# 7seg.net
KiCad netlist of a schematic drawn in EAGLE
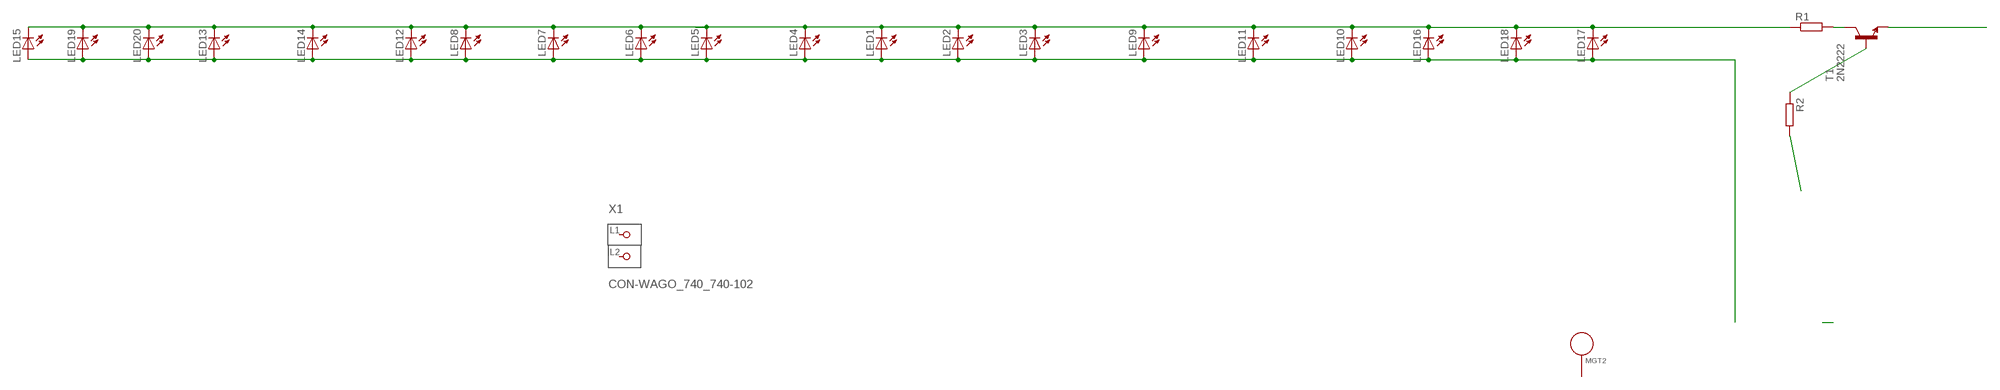
[diagram p0: schematic, sheet 1]
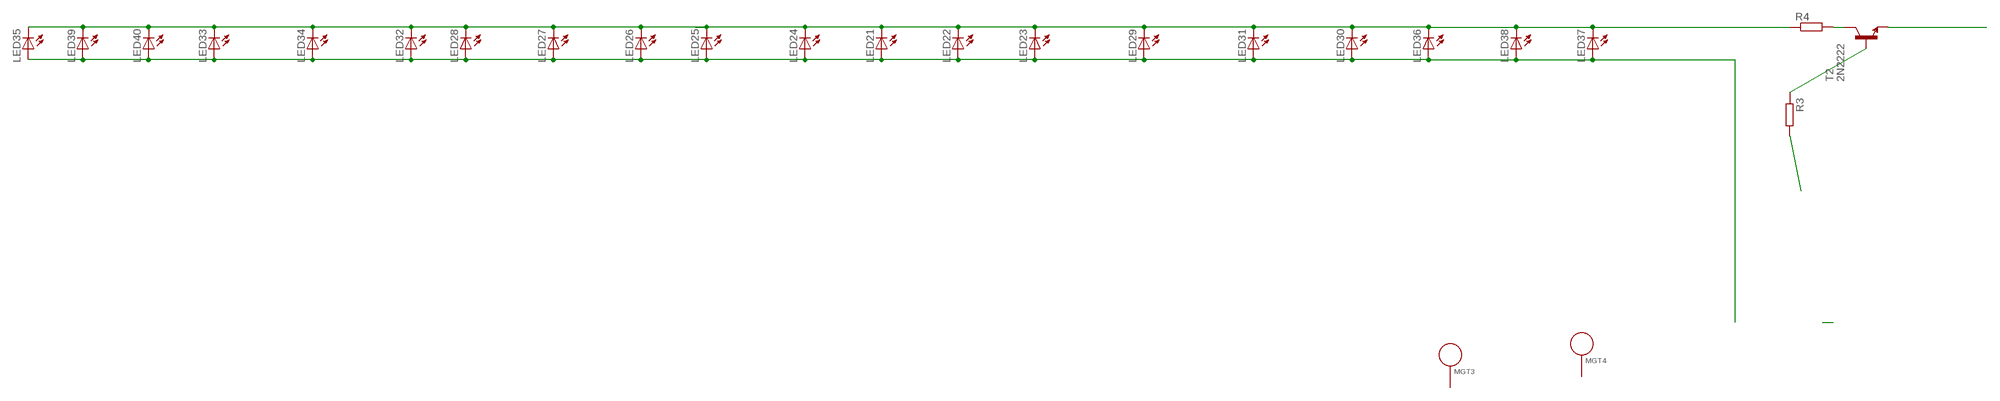
[diagram p1: schematic, sheet 2]
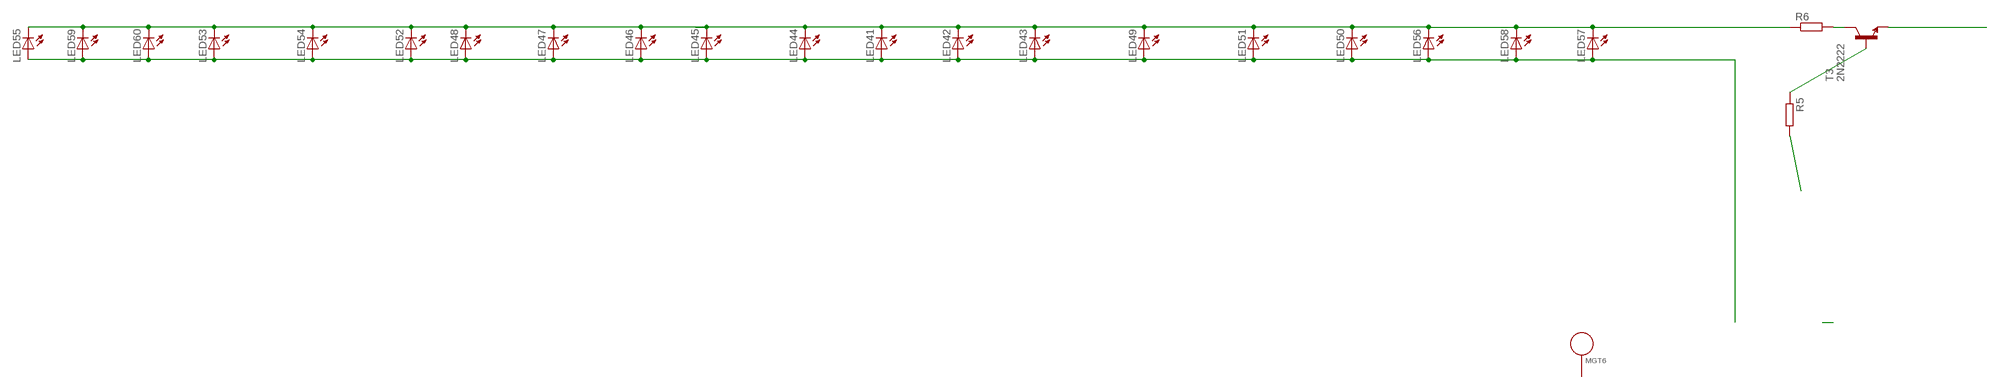
[diagram p2: schematic, sheet 3]
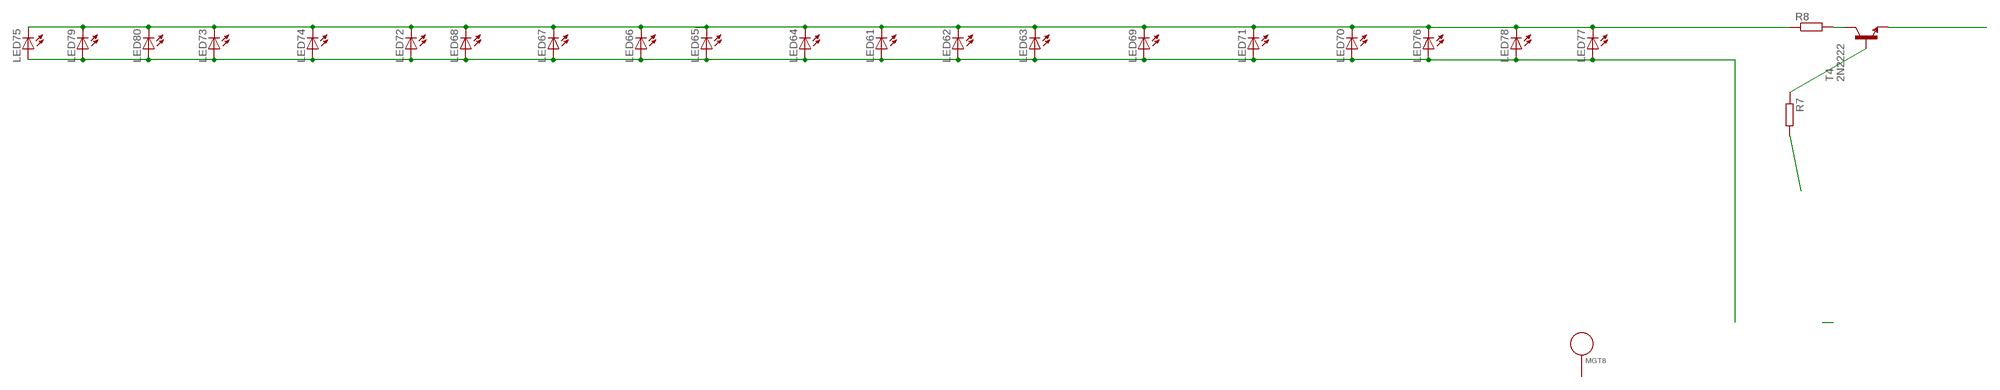
[diagram p3: schematic, sheet 4]
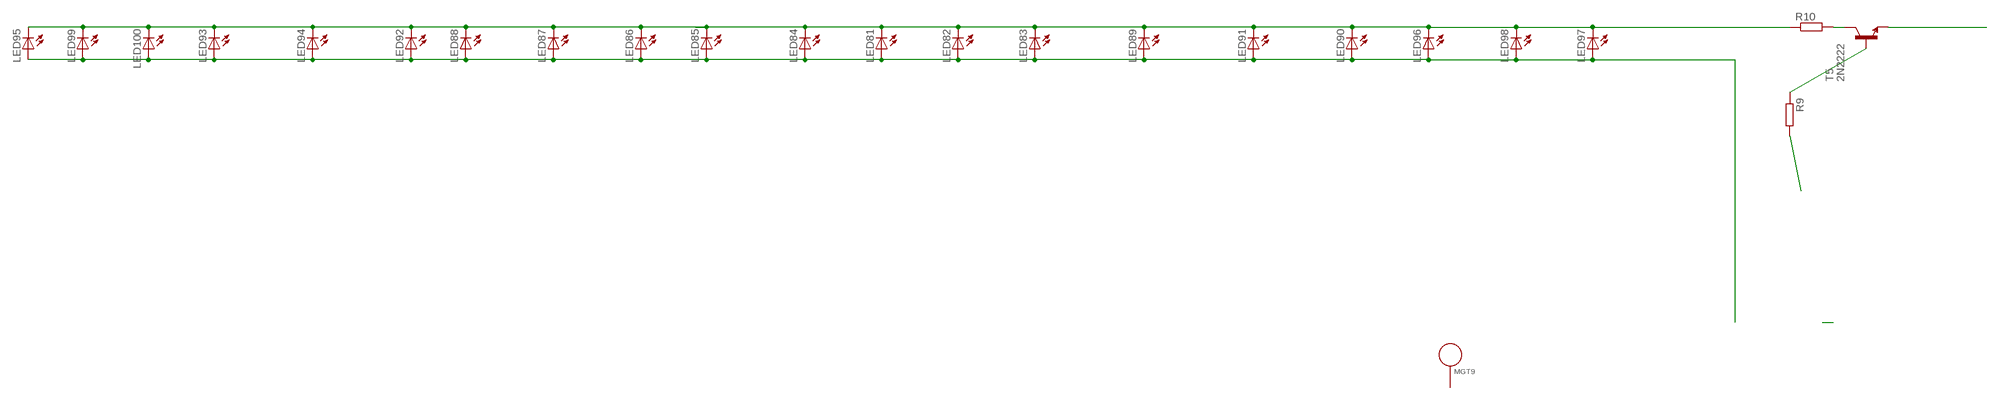
[diagram p4: schematic, sheet 5]
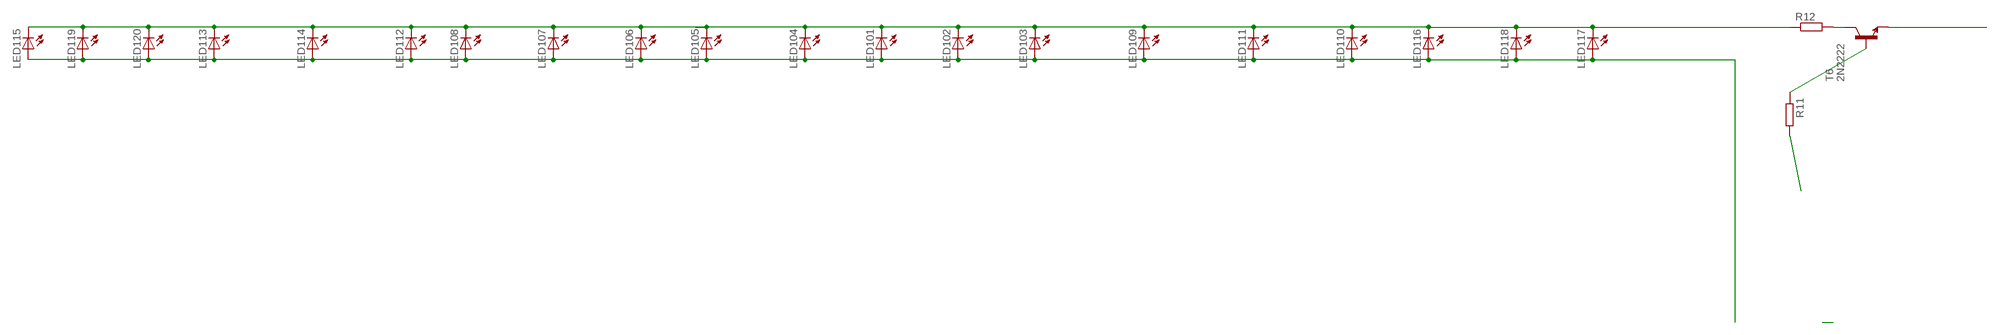
[diagram p5: schematic, sheet 6]
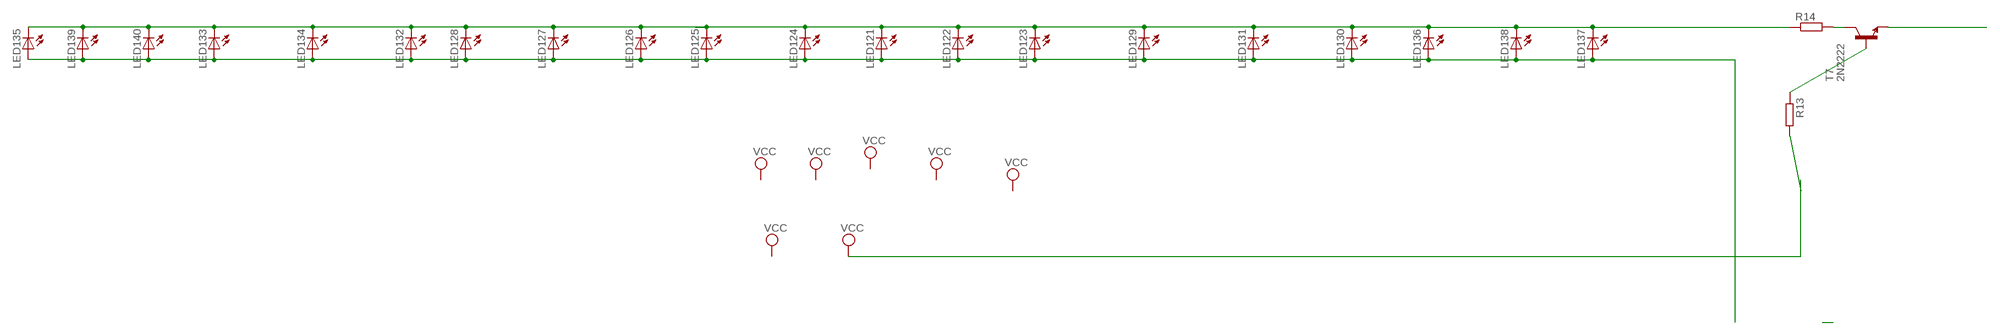
[diagram p6: schematic, sheet 7]

(export (version "E")
  (design (tool "Eeschema 10.0.6"))
  (components
    (comp (ref "LED21")
      (value "LED5MM")
      (footprint "eagle-import:LED5MM")
      (libsource (lib "eagle-import") (part "LED5MM"))
    )
    (comp (ref "LED22")
      (value "LED5MM")
      (footprint "eagle-import:LED5MM")
      (libsource (lib "eagle-import") (part "LED5MM"))
    )
    (comp (ref "LED23")
      (value "LED5MM")
      (footprint "eagle-import:LED5MM")
      (libsource (lib "eagle-import") (part "LED5MM"))
    )
    (comp (ref "LED24")
      (value "LED5MM")
      (footprint "eagle-import:LED5MM")
      (libsource (lib "eagle-import") (part "LED5MM"))
    )
    (comp (ref "LED25")
      (value "LED5MM")
      (footprint "eagle-import:LED5MM")
      (libsource (lib "eagle-import") (part "LED5MM"))
    )
    (comp (ref "LED26")
      (value "LED5MM")
      (footprint "eagle-import:LED5MM")
      (libsource (lib "eagle-import") (part "LED5MM"))
    )
    (comp (ref "LED27")
      (value "LED5MM")
      (footprint "eagle-import:LED5MM")
      (libsource (lib "eagle-import") (part "LED5MM"))
    )
    (comp (ref "LED28")
      (value "LED5MM")
      (footprint "eagle-import:LED5MM")
      (libsource (lib "eagle-import") (part "LED5MM"))
    )
    (comp (ref "LED29")
      (value "LED5MM")
      (footprint "eagle-import:LED5MM")
      (libsource (lib "eagle-import") (part "LED5MM"))
    )
    (comp (ref "LED30")
      (value "LED5MM")
      (footprint "eagle-import:LED5MM")
      (libsource (lib "eagle-import") (part "LED5MM"))
    )
    (comp (ref "LED31")
      (value "LED5MM")
      (footprint "eagle-import:LED5MM")
      (libsource (lib "eagle-import") (part "LED5MM"))
    )
    (comp (ref "LED32")
      (value "LED5MM")
      (footprint "eagle-import:LED5MM")
      (libsource (lib "eagle-import") (part "LED5MM"))
    )
    (comp (ref "LED33")
      (value "LED5MM")
      (footprint "eagle-import:LED5MM")
      (libsource (lib "eagle-import") (part "LED5MM"))
    )
    (comp (ref "LED34")
      (value "LED5MM")
      (footprint "eagle-import:LED5MM")
      (libsource (lib "eagle-import") (part "LED5MM"))
    )
    (comp (ref "LED35")
      (value "LED5MM")
      (footprint "eagle-import:LED5MM")
      (libsource (lib "eagle-import") (part "LED5MM"))
    )
    (comp (ref "LED36")
      (value "LED5MM")
      (footprint "eagle-import:LED5MM")
      (libsource (lib "eagle-import") (part "LED5MM"))
    )
    (comp (ref "LED37")
      (value "LED5MM")
      (footprint "eagle-import:LED5MM")
      (libsource (lib "eagle-import") (part "LED5MM"))
    )
    (comp (ref "LED38")
      (value "LED5MM")
      (footprint "eagle-import:LED5MM")
      (libsource (lib "eagle-import") (part "LED5MM"))
    )
    (comp (ref "LED39")
      (value "LED5MM")
      (footprint "eagle-import:LED5MM")
      (libsource (lib "eagle-import") (part "LED5MM"))
    )
    (comp (ref "LED40")
      (value "LED5MM")
      (footprint "eagle-import:LED5MM")
      (libsource (lib "eagle-import") (part "LED5MM"))
    )
    (comp (ref "MGT3")
      (value "BEAGLEBONEBLACK_MOUNTING_HOLE")
      (footprint "eagle-import:BEAGLEBONEBLACK_MOUNTING_HOLE")
      (libsource (lib "eagle-import") (part "BEAGLEBONEBLACK_MOUNTING_HOLE"))
    )
    (comp (ref "MGT4")
      (value "BEAGLEBONEBLACK_MOUNTING_HOLE")
      (footprint "eagle-import:BEAGLEBONEBLACK_MOUNTING_HOLE")
      (libsource (lib "eagle-import") (part "BEAGLEBONEBLACK_MOUNTING_HOLE"))
    )
    (comp (ref "R3")
      (value "R-EU_0207/10")
      (footprint "eagle-import:0207_10")
      (libsource (lib "eagle-import") (part "R-EU_0207/10"))
    )
    (comp (ref "R4")
      (value "R-EU_0207/10")
      (footprint "eagle-import:0207_10")
      (libsource (lib "eagle-import") (part "R-EU_0207/10"))
    )
    (comp (ref "T2")
      (value "2N2222")
      (footprint "eagle-import:TO92-EBC-OVAL")
      (libsource (lib "eagle-import") (part "2N2222"))
    )
    (comp (ref "LED41")
      (value "LED5MM")
      (footprint "eagle-import:LED5MM")
      (libsource (lib "eagle-import") (part "LED5MM"))
    )
    (comp (ref "LED42")
      (value "LED5MM")
      (footprint "eagle-import:LED5MM")
      (libsource (lib "eagle-import") (part "LED5MM"))
    )
    (comp (ref "LED43")
      (value "LED5MM")
      (footprint "eagle-import:LED5MM")
      (libsource (lib "eagle-import") (part "LED5MM"))
    )
    (comp (ref "LED44")
      (value "LED5MM")
      (footprint "eagle-import:LED5MM")
      (libsource (lib "eagle-import") (part "LED5MM"))
    )
    (comp (ref "LED45")
      (value "LED5MM")
      (footprint "eagle-import:LED5MM")
      (libsource (lib "eagle-import") (part "LED5MM"))
    )
    (comp (ref "LED46")
      (value "LED5MM")
      (footprint "eagle-import:LED5MM")
      (libsource (lib "eagle-import") (part "LED5MM"))
    )
    (comp (ref "LED47")
      (value "LED5MM")
      (footprint "eagle-import:LED5MM")
      (libsource (lib "eagle-import") (part "LED5MM"))
    )
    (comp (ref "LED48")
      (value "LED5MM")
      (footprint "eagle-import:LED5MM")
      (libsource (lib "eagle-import") (part "LED5MM"))
    )
    (comp (ref "LED49")
      (value "LED5MM")
      (footprint "eagle-import:LED5MM")
      (libsource (lib "eagle-import") (part "LED5MM"))
    )
    (comp (ref "LED50")
      (value "LED5MM")
      (footprint "eagle-import:LED5MM")
      (libsource (lib "eagle-import") (part "LED5MM"))
    )
    (comp (ref "LED51")
      (value "LED5MM")
      (footprint "eagle-import:LED5MM")
      (libsource (lib "eagle-import") (part "LED5MM"))
    )
    (comp (ref "LED52")
      (value "LED5MM")
      (footprint "eagle-import:LED5MM")
      (libsource (lib "eagle-import") (part "LED5MM"))
    )
    (comp (ref "LED53")
      (value "LED5MM")
      (footprint "eagle-import:LED5MM")
      (libsource (lib "eagle-import") (part "LED5MM"))
    )
    (comp (ref "LED54")
      (value "LED5MM")
      (footprint "eagle-import:LED5MM")
      (libsource (lib "eagle-import") (part "LED5MM"))
    )
    (comp (ref "LED55")
      (value "LED5MM")
      (footprint "eagle-import:LED5MM")
      (libsource (lib "eagle-import") (part "LED5MM"))
    )
    (comp (ref "LED56")
      (value "LED5MM")
      (footprint "eagle-import:LED5MM")
      (libsource (lib "eagle-import") (part "LED5MM"))
    )
    (comp (ref "LED57")
      (value "LED5MM")
      (footprint "eagle-import:LED5MM")
      (libsource (lib "eagle-import") (part "LED5MM"))
    )
    (comp (ref "LED58")
      (value "LED5MM")
      (footprint "eagle-import:LED5MM")
      (libsource (lib "eagle-import") (part "LED5MM"))
    )
    (comp (ref "LED59")
      (value "LED5MM")
      (footprint "eagle-import:LED5MM")
      (libsource (lib "eagle-import") (part "LED5MM"))
    )
    (comp (ref "LED60")
      (value "LED5MM")
      (footprint "eagle-import:LED5MM")
      (libsource (lib "eagle-import") (part "LED5MM"))
    )
    (comp (ref "MGT6")
      (value "BEAGLEBONEBLACK_MOUNTING_HOLE")
      (footprint "eagle-import:BEAGLEBONEBLACK_MOUNTING_HOLE")
      (libsource (lib "eagle-import") (part "BEAGLEBONEBLACK_MOUNTING_HOLE"))
    )
    (comp (ref "R5")
      (value "R-EU_0207/10")
      (footprint "eagle-import:0207_10")
      (libsource (lib "eagle-import") (part "R-EU_0207/10"))
    )
    (comp (ref "R6")
      (value "R-EU_0207/10")
      (footprint "eagle-import:0207_10")
      (libsource (lib "eagle-import") (part "R-EU_0207/10"))
    )
    (comp (ref "T3")
      (value "2N2222")
      (footprint "eagle-import:TO92-EBC-OVAL")
      (libsource (lib "eagle-import") (part "2N2222"))
    )
    (comp (ref "LED61")
      (value "LED5MM")
      (footprint "eagle-import:LED5MM")
      (libsource (lib "eagle-import") (part "LED5MM"))
    )
    (comp (ref "LED62")
      (value "LED5MM")
      (footprint "eagle-import:LED5MM")
      (libsource (lib "eagle-import") (part "LED5MM"))
    )
    (comp (ref "LED63")
      (value "LED5MM")
      (footprint "eagle-import:LED5MM")
      (libsource (lib "eagle-import") (part "LED5MM"))
    )
    (comp (ref "LED64")
      (value "LED5MM")
      (footprint "eagle-import:LED5MM")
      (libsource (lib "eagle-import") (part "LED5MM"))
    )
    (comp (ref "LED65")
      (value "LED5MM")
      (footprint "eagle-import:LED5MM")
      (libsource (lib "eagle-import") (part "LED5MM"))
    )
    (comp (ref "LED66")
      (value "LED5MM")
      (footprint "eagle-import:LED5MM")
      (libsource (lib "eagle-import") (part "LED5MM"))
    )
    (comp (ref "LED67")
      (value "LED5MM")
      (footprint "eagle-import:LED5MM")
      (libsource (lib "eagle-import") (part "LED5MM"))
    )
    (comp (ref "LED68")
      (value "LED5MM")
      (footprint "eagle-import:LED5MM")
      (libsource (lib "eagle-import") (part "LED5MM"))
    )
    (comp (ref "LED69")
      (value "LED5MM")
      (footprint "eagle-import:LED5MM")
      (libsource (lib "eagle-import") (part "LED5MM"))
    )
    (comp (ref "LED70")
      (value "LED5MM")
      (footprint "eagle-import:LED5MM")
      (libsource (lib "eagle-import") (part "LED5MM"))
    )
    (comp (ref "LED71")
      (value "LED5MM")
      (footprint "eagle-import:LED5MM")
      (libsource (lib "eagle-import") (part "LED5MM"))
    )
    (comp (ref "LED72")
      (value "LED5MM")
      (footprint "eagle-import:LED5MM")
      (libsource (lib "eagle-import") (part "LED5MM"))
    )
    (comp (ref "LED73")
      (value "LED5MM")
      (footprint "eagle-import:LED5MM")
      (libsource (lib "eagle-import") (part "LED5MM"))
    )
    (comp (ref "LED74")
      (value "LED5MM")
      (footprint "eagle-import:LED5MM")
      (libsource (lib "eagle-import") (part "LED5MM"))
    )
    (comp (ref "LED75")
      (value "LED5MM")
      (footprint "eagle-import:LED5MM")
      (libsource (lib "eagle-import") (part "LED5MM"))
    )
    (comp (ref "LED76")
      (value "LED5MM")
      (footprint "eagle-import:LED5MM")
      (libsource (lib "eagle-import") (part "LED5MM"))
    )
    (comp (ref "LED77")
      (value "LED5MM")
      (footprint "eagle-import:LED5MM")
      (libsource (lib "eagle-import") (part "LED5MM"))
    )
    (comp (ref "LED78")
      (value "LED5MM")
      (footprint "eagle-import:LED5MM")
      (libsource (lib "eagle-import") (part "LED5MM"))
    )
    (comp (ref "LED79")
      (value "LED5MM")
      (footprint "eagle-import:LED5MM")
      (libsource (lib "eagle-import") (part "LED5MM"))
    )
    (comp (ref "LED80")
      (value "LED5MM")
      (footprint "eagle-import:LED5MM")
      (libsource (lib "eagle-import") (part "LED5MM"))
    )
    (comp (ref "MGT8")
      (value "BEAGLEBONEBLACK_MOUNTING_HOLE")
      (footprint "eagle-import:BEAGLEBONEBLACK_MOUNTING_HOLE")
      (libsource (lib "eagle-import") (part "BEAGLEBONEBLACK_MOUNTING_HOLE"))
    )
    (comp (ref "R7")
      (value "R-EU_0207/10")
      (footprint "eagle-import:0207_10")
      (libsource (lib "eagle-import") (part "R-EU_0207/10"))
    )
    (comp (ref "R8")
      (value "R-EU_0207/10")
      (footprint "eagle-import:0207_10")
      (libsource (lib "eagle-import") (part "R-EU_0207/10"))
    )
    (comp (ref "T4")
      (value "2N2222")
      (footprint "eagle-import:TO92-EBC-OVAL")
      (libsource (lib "eagle-import") (part "2N2222"))
    )
    (comp (ref "LED101")
      (value "LED5MM")
      (footprint "eagle-import:LED5MM")
      (libsource (lib "eagle-import") (part "LED5MM"))
    )
    (comp (ref "LED102")
      (value "LED5MM")
      (footprint "eagle-import:LED5MM")
      (libsource (lib "eagle-import") (part "LED5MM"))
    )
    (comp (ref "LED103")
      (value "LED5MM")
      (footprint "eagle-import:LED5MM")
      (libsource (lib "eagle-import") (part "LED5MM"))
    )
    (comp (ref "LED104")
      (value "LED5MM")
      (footprint "eagle-import:LED5MM")
      (libsource (lib "eagle-import") (part "LED5MM"))
    )
    (comp (ref "LED105")
      (value "LED5MM")
      (footprint "eagle-import:LED5MM")
      (libsource (lib "eagle-import") (part "LED5MM"))
    )
    (comp (ref "LED106")
      (value "LED5MM")
      (footprint "eagle-import:LED5MM")
      (libsource (lib "eagle-import") (part "LED5MM"))
    )
    (comp (ref "LED107")
      (value "LED5MM")
      (footprint "eagle-import:LED5MM")
      (libsource (lib "eagle-import") (part "LED5MM"))
    )
    (comp (ref "LED108")
      (value "LED5MM")
      (footprint "eagle-import:LED5MM")
      (libsource (lib "eagle-import") (part "LED5MM"))
    )
    (comp (ref "LED109")
      (value "LED5MM")
      (footprint "eagle-import:LED5MM")
      (libsource (lib "eagle-import") (part "LED5MM"))
    )
    (comp (ref "LED110")
      (value "LED5MM")
      (footprint "eagle-import:LED5MM")
      (libsource (lib "eagle-import") (part "LED5MM"))
    )
    (comp (ref "LED111")
      (value "LED5MM")
      (footprint "eagle-import:LED5MM")
      (libsource (lib "eagle-import") (part "LED5MM"))
    )
    (comp (ref "LED112")
      (value "LED5MM")
      (footprint "eagle-import:LED5MM")
      (libsource (lib "eagle-import") (part "LED5MM"))
    )
    (comp (ref "LED113")
      (value "LED5MM")
      (footprint "eagle-import:LED5MM")
      (libsource (lib "eagle-import") (part "LED5MM"))
    )
    (comp (ref "LED114")
      (value "LED5MM")
      (footprint "eagle-import:LED5MM")
      (libsource (lib "eagle-import") (part "LED5MM"))
    )
    (comp (ref "LED115")
      (value "LED5MM")
      (footprint "eagle-import:LED5MM")
      (libsource (lib "eagle-import") (part "LED5MM"))
    )
    (comp (ref "LED116")
      (value "LED5MM")
      (footprint "eagle-import:LED5MM")
      (libsource (lib "eagle-import") (part "LED5MM"))
    )
    (comp (ref "LED117")
      (value "LED5MM")
      (footprint "eagle-import:LED5MM")
      (libsource (lib "eagle-import") (part "LED5MM"))
    )
    (comp (ref "LED118")
      (value "LED5MM")
      (footprint "eagle-import:LED5MM")
      (libsource (lib "eagle-import") (part "LED5MM"))
    )
    (comp (ref "LED119")
      (value "LED5MM")
      (footprint "eagle-import:LED5MM")
      (libsource (lib "eagle-import") (part "LED5MM"))
    )
    (comp (ref "LED120")
      (value "LED5MM")
      (footprint "eagle-import:LED5MM")
      (libsource (lib "eagle-import") (part "LED5MM"))
    )
    (comp (ref "R11")
      (value "R-EU_0207/10")
      (footprint "eagle-import:0207_10")
      (libsource (lib "eagle-import") (part "R-EU_0207/10"))
    )
    (comp (ref "R12")
      (value "R-EU_0207/10")
      (footprint "eagle-import:0207_10")
      (libsource (lib "eagle-import") (part "R-EU_0207/10"))
    )
    (comp (ref "T6")
      (value "2N2222")
      (footprint "eagle-import:TO92-EBC-OVAL")
      (libsource (lib "eagle-import") (part "2N2222"))
    )
    (comp (ref "LED1")
      (value "LED5MM")
      (footprint "eagle-import:LED5MM")
      (libsource (lib "eagle-import") (part "LED5MM"))
    )
    (comp (ref "LED2")
      (value "LED5MM")
      (footprint "eagle-import:LED5MM")
      (libsource (lib "eagle-import") (part "LED5MM"))
    )
    (comp (ref "LED3")
      (value "LED5MM")
      (footprint "eagle-import:LED5MM")
      (libsource (lib "eagle-import") (part "LED5MM"))
    )
    (comp (ref "LED4")
      (value "LED5MM")
      (footprint "eagle-import:LED5MM")
      (libsource (lib "eagle-import") (part "LED5MM"))
    )
    (comp (ref "LED5")
      (value "LED5MM")
      (footprint "eagle-import:LED5MM")
      (libsource (lib "eagle-import") (part "LED5MM"))
    )
    (comp (ref "LED6")
      (value "LED5MM")
      (footprint "eagle-import:LED5MM")
      (libsource (lib "eagle-import") (part "LED5MM"))
    )
    (comp (ref "LED7")
      (value "LED5MM")
      (footprint "eagle-import:LED5MM")
      (libsource (lib "eagle-import") (part "LED5MM"))
    )
    (comp (ref "LED8")
      (value "LED5MM")
      (footprint "eagle-import:LED5MM")
      (libsource (lib "eagle-import") (part "LED5MM"))
    )
    (comp (ref "LED9")
      (value "LED5MM")
      (footprint "eagle-import:LED5MM")
      (libsource (lib "eagle-import") (part "LED5MM"))
    )
    (comp (ref "LED10")
      (value "LED5MM")
      (footprint "eagle-import:LED5MM")
      (libsource (lib "eagle-import") (part "LED5MM"))
    )
    (comp (ref "LED11")
      (value "LED5MM")
      (footprint "eagle-import:LED5MM")
      (libsource (lib "eagle-import") (part "LED5MM"))
    )
    (comp (ref "LED12")
      (value "LED5MM")
      (footprint "eagle-import:LED5MM")
      (libsource (lib "eagle-import") (part "LED5MM"))
    )
    (comp (ref "LED13")
      (value "LED5MM")
      (footprint "eagle-import:LED5MM")
      (libsource (lib "eagle-import") (part "LED5MM"))
    )
    (comp (ref "LED14")
      (value "LED5MM")
      (footprint "eagle-import:LED5MM")
      (libsource (lib "eagle-import") (part "LED5MM"))
    )
    (comp (ref "LED15")
      (value "LED5MM")
      (footprint "eagle-import:LED5MM")
      (libsource (lib "eagle-import") (part "LED5MM"))
    )
    (comp (ref "LED16")
      (value "LED5MM")
      (footprint "eagle-import:LED5MM")
      (libsource (lib "eagle-import") (part "LED5MM"))
    )
    (comp (ref "LED17")
      (value "LED5MM")
      (footprint "eagle-import:LED5MM")
      (libsource (lib "eagle-import") (part "LED5MM"))
    )
    (comp (ref "LED18")
      (value "LED5MM")
      (footprint "eagle-import:LED5MM")
      (libsource (lib "eagle-import") (part "LED5MM"))
    )
    (comp (ref "LED19")
      (value "LED5MM")
      (footprint "eagle-import:LED5MM")
      (libsource (lib "eagle-import") (part "LED5MM"))
    )
    (comp (ref "LED20")
      (value "LED5MM")
      (footprint "eagle-import:LED5MM")
      (libsource (lib "eagle-import") (part "LED5MM"))
    )
    (comp (ref "MGT2")
      (value "BEAGLEBONEBLACK_MOUNTING_HOLE")
      (footprint "eagle-import:BEAGLEBONEBLACK_MOUNTING_HOLE")
      (libsource (lib "eagle-import") (part "BEAGLEBONEBLACK_MOUNTING_HOLE"))
    )
    (comp (ref "R1")
      (value "R-EU_0207/10")
      (footprint "eagle-import:0207_10")
      (libsource (lib "eagle-import") (part "R-EU_0207/10"))
    )
    (comp (ref "R2")
      (value "R-EU_0207/10")
      (footprint "eagle-import:0207_10")
      (libsource (lib "eagle-import") (part "R-EU_0207/10"))
    )
    (comp (ref "T1")
      (value "2N2222")
      (footprint "eagle-import:TO92-EBC-OVAL")
      (libsource (lib "eagle-import") (part "2N2222"))
    )
    (comp (ref "X1")
      (value "CON-WAGO_740_740-102")
      (footprint "eagle-import:CON-WAGO_740_P-740-102")
      (libsource (lib "eagle-import") (part "CON-WAGO_740_740-102"))
    )
    (comp (ref "LED121")
      (value "LED5MM")
      (footprint "eagle-import:LED5MM")
      (libsource (lib "eagle-import") (part "LED5MM"))
    )
    (comp (ref "LED122")
      (value "LED5MM")
      (footprint "eagle-import:LED5MM")
      (libsource (lib "eagle-import") (part "LED5MM"))
    )
    (comp (ref "LED123")
      (value "LED5MM")
      (footprint "eagle-import:LED5MM")
      (libsource (lib "eagle-import") (part "LED5MM"))
    )
    (comp (ref "LED124")
      (value "LED5MM")
      (footprint "eagle-import:LED5MM")
      (libsource (lib "eagle-import") (part "LED5MM"))
    )
    (comp (ref "LED125")
      (value "LED5MM")
      (footprint "eagle-import:LED5MM")
      (libsource (lib "eagle-import") (part "LED5MM"))
    )
    (comp (ref "LED126")
      (value "LED5MM")
      (footprint "eagle-import:LED5MM")
      (libsource (lib "eagle-import") (part "LED5MM"))
    )
    (comp (ref "LED127")
      (value "LED5MM")
      (footprint "eagle-import:LED5MM")
      (libsource (lib "eagle-import") (part "LED5MM"))
    )
    (comp (ref "LED128")
      (value "LED5MM")
      (footprint "eagle-import:LED5MM")
      (libsource (lib "eagle-import") (part "LED5MM"))
    )
    (comp (ref "LED129")
      (value "LED5MM")
      (footprint "eagle-import:LED5MM")
      (libsource (lib "eagle-import") (part "LED5MM"))
    )
    (comp (ref "LED130")
      (value "LED5MM")
      (footprint "eagle-import:LED5MM")
      (libsource (lib "eagle-import") (part "LED5MM"))
    )
    (comp (ref "LED131")
      (value "LED5MM")
      (footprint "eagle-import:LED5MM")
      (libsource (lib "eagle-import") (part "LED5MM"))
    )
    (comp (ref "LED132")
      (value "LED5MM")
      (footprint "eagle-import:LED5MM")
      (libsource (lib "eagle-import") (part "LED5MM"))
    )
    (comp (ref "LED133")
      (value "LED5MM")
      (footprint "eagle-import:LED5MM")
      (libsource (lib "eagle-import") (part "LED5MM"))
    )
    (comp (ref "LED134")
      (value "LED5MM")
      (footprint "eagle-import:LED5MM")
      (libsource (lib "eagle-import") (part "LED5MM"))
    )
    (comp (ref "LED135")
      (value "LED5MM")
      (footprint "eagle-import:LED5MM")
      (libsource (lib "eagle-import") (part "LED5MM"))
    )
    (comp (ref "LED136")
      (value "LED5MM")
      (footprint "eagle-import:LED5MM")
      (libsource (lib "eagle-import") (part "LED5MM"))
    )
    (comp (ref "LED137")
      (value "LED5MM")
      (footprint "eagle-import:LED5MM")
      (libsource (lib "eagle-import") (part "LED5MM"))
    )
    (comp (ref "LED138")
      (value "LED5MM")
      (footprint "eagle-import:LED5MM")
      (libsource (lib "eagle-import") (part "LED5MM"))
    )
    (comp (ref "LED139")
      (value "LED5MM")
      (footprint "eagle-import:LED5MM")
      (libsource (lib "eagle-import") (part "LED5MM"))
    )
    (comp (ref "LED140")
      (value "LED5MM")
      (footprint "eagle-import:LED5MM")
      (libsource (lib "eagle-import") (part "LED5MM"))
    )
    (comp (ref "R13")
      (value "R-EU_0207/10")
      (footprint "eagle-import:0207_10")
      (libsource (lib "eagle-import") (part "R-EU_0207/10"))
    )
    (comp (ref "R14")
      (value "R-EU_0207/10")
      (footprint "eagle-import:0207_10")
      (libsource (lib "eagle-import") (part "R-EU_0207/10"))
    )
    (comp (ref "T7")
      (value "2N2222")
      (footprint "eagle-import:TO92-EBC-OVAL")
      (libsource (lib "eagle-import") (part "2N2222"))
    )
    (comp (ref "LED81")
      (value "LED5MM")
      (footprint "eagle-import:LED5MM")
      (libsource (lib "eagle-import") (part "LED5MM"))
    )
    (comp (ref "LED82")
      (value "LED5MM")
      (footprint "eagle-import:LED5MM")
      (libsource (lib "eagle-import") (part "LED5MM"))
    )
    (comp (ref "LED83")
      (value "LED5MM")
      (footprint "eagle-import:LED5MM")
      (libsource (lib "eagle-import") (part "LED5MM"))
    )
    (comp (ref "LED84")
      (value "LED5MM")
      (footprint "eagle-import:LED5MM")
      (libsource (lib "eagle-import") (part "LED5MM"))
    )
    (comp (ref "LED85")
      (value "LED5MM")
      (footprint "eagle-import:LED5MM")
      (libsource (lib "eagle-import") (part "LED5MM"))
    )
    (comp (ref "LED86")
      (value "LED5MM")
      (footprint "eagle-import:LED5MM")
      (libsource (lib "eagle-import") (part "LED5MM"))
    )
    (comp (ref "LED87")
      (value "LED5MM")
      (footprint "eagle-import:LED5MM")
      (libsource (lib "eagle-import") (part "LED5MM"))
    )
    (comp (ref "LED88")
      (value "LED5MM")
      (footprint "eagle-import:LED5MM")
      (libsource (lib "eagle-import") (part "LED5MM"))
    )
    (comp (ref "LED89")
      (value "LED5MM")
      (footprint "eagle-import:LED5MM")
      (libsource (lib "eagle-import") (part "LED5MM"))
    )
    (comp (ref "LED90")
      (value "LED5MM")
      (footprint "eagle-import:LED5MM")
      (libsource (lib "eagle-import") (part "LED5MM"))
    )
    (comp (ref "LED91")
      (value "LED5MM")
      (footprint "eagle-import:LED5MM")
      (libsource (lib "eagle-import") (part "LED5MM"))
    )
    (comp (ref "LED92")
      (value "LED5MM")
      (footprint "eagle-import:LED5MM")
      (libsource (lib "eagle-import") (part "LED5MM"))
    )
    (comp (ref "LED93")
      (value "LED5MM")
      (footprint "eagle-import:LED5MM")
      (libsource (lib "eagle-import") (part "LED5MM"))
    )
    (comp (ref "LED94")
      (value "LED5MM")
      (footprint "eagle-import:LED5MM")
      (libsource (lib "eagle-import") (part "LED5MM"))
    )
    (comp (ref "LED95")
      (value "LED5MM")
      (footprint "eagle-import:LED5MM")
      (libsource (lib "eagle-import") (part "LED5MM"))
    )
    (comp (ref "LED96")
      (value "LED5MM")
      (footprint "eagle-import:LED5MM")
      (libsource (lib "eagle-import") (part "LED5MM"))
    )
    (comp (ref "LED97")
      (value "LED5MM")
      (footprint "eagle-import:LED5MM")
      (libsource (lib "eagle-import") (part "LED5MM"))
    )
    (comp (ref "LED98")
      (value "LED5MM")
      (footprint "eagle-import:LED5MM")
      (libsource (lib "eagle-import") (part "LED5MM"))
    )
    (comp (ref "LED99")
      (value "LED5MM")
      (footprint "eagle-import:LED5MM")
      (libsource (lib "eagle-import") (part "LED5MM"))
    )
    (comp (ref "LED100")
      (value "LED5MM")
      (footprint "eagle-import:LED5MM")
      (libsource (lib "eagle-import") (part "LED5MM"))
    )
    (comp (ref "MGT9")
      (value "BEAGLEBONEBLACK_MOUNTING_HOLE")
      (footprint "eagle-import:BEAGLEBONEBLACK_MOUNTING_HOLE")
      (libsource (lib "eagle-import") (part "BEAGLEBONEBLACK_MOUNTING_HOLE"))
    )
    (comp (ref "R9")
      (value "R-EU_0207/10")
      (footprint "eagle-import:0207_10")
      (libsource (lib "eagle-import") (part "R-EU_0207/10"))
    )
    (comp (ref "R10")
      (value "R-EU_0207/10")
      (footprint "eagle-import:0207_10")
      (libsource (lib "eagle-import") (part "R-EU_0207/10"))
    )
    (comp (ref "T5")
      (value "2N2222")
      (footprint "eagle-import:TO92-EBC-OVAL")
      (libsource (lib "eagle-import") (part "2N2222"))
    )
  )
  (nets
    (net (code "1") (name "Net-(LED1-C)") (class "Default")
      (node (ref "LED1") (pin "K") (pinfunction "C_K") (pintype "passive"))
      (node (ref "LED10") (pin "K") (pinfunction "C_K") (pintype "passive"))
      (node (ref "LED11") (pin "K") (pinfunction "C_K") (pintype "passive"))
      (node (ref "LED12") (pin "K") (pinfunction "C_K") (pintype "passive"))
      (node (ref "LED13") (pin "K") (pinfunction "C_K") (pintype "passive"))
      (node (ref "LED14") (pin "K") (pinfunction "C_K") (pintype "passive"))
      (node (ref "LED15") (pin "K") (pinfunction "C_K") (pintype "passive"))
      (node (ref "LED16") (pin "K") (pinfunction "C_K") (pintype "passive"))
      (node (ref "LED17") (pin "K") (pinfunction "C_K") (pintype "passive"))
      (node (ref "LED18") (pin "K") (pinfunction "C_K") (pintype "passive"))
      (node (ref "LED19") (pin "K") (pinfunction "C_K") (pintype "passive"))
      (node (ref "LED2") (pin "K") (pinfunction "C_K") (pintype "passive"))
      (node (ref "LED20") (pin "K") (pinfunction "C_K") (pintype "passive"))
      (node (ref "LED3") (pin "K") (pinfunction "C_K") (pintype "passive"))
      (node (ref "LED4") (pin "K") (pinfunction "C_K") (pintype "passive"))
      (node (ref "LED5") (pin "K") (pinfunction "C_K") (pintype "passive"))
      (node (ref "LED6") (pin "K") (pinfunction "C_K") (pintype "passive"))
      (node (ref "LED7") (pin "K") (pinfunction "C_K") (pintype "passive"))
      (node (ref "LED8") (pin "K") (pinfunction "C_K") (pintype "passive"))
      (node (ref "LED9") (pin "K") (pinfunction "C_K") (pintype "passive"))
      (node (ref "R1") (pin "1") (pinfunction "1_1") (pintype "passive"))
    )
    (net (code "2") (name "Net-(LED1-PadA)") (class "Default")
      (node (ref "LED1") (pin "A") (pinfunction "A_A") (pintype "passive"))
      (node (ref "LED10") (pin "A") (pinfunction "A_A") (pintype "passive"))
      (node (ref "LED11") (pin "A") (pinfunction "A_A") (pintype "passive"))
      (node (ref "LED12") (pin "A") (pinfunction "A_A") (pintype "passive"))
      (node (ref "LED13") (pin "A") (pinfunction "A_A") (pintype "passive"))
      (node (ref "LED14") (pin "A") (pinfunction "A_A") (pintype "passive"))
      (node (ref "LED15") (pin "A") (pinfunction "A_A") (pintype "passive"))
      (node (ref "LED16") (pin "A") (pinfunction "A_A") (pintype "passive"))
      (node (ref "LED17") (pin "A") (pinfunction "A_A") (pintype "passive"))
      (node (ref "LED18") (pin "A") (pinfunction "A_A") (pintype "passive"))
      (node (ref "LED19") (pin "A") (pinfunction "A_A") (pintype "passive"))
      (node (ref "LED2") (pin "A") (pinfunction "A_A") (pintype "passive"))
      (node (ref "LED20") (pin "A") (pinfunction "A_A") (pintype "passive"))
      (node (ref "LED3") (pin "A") (pinfunction "A_A") (pintype "passive"))
      (node (ref "LED4") (pin "A") (pinfunction "A_A") (pintype "passive"))
      (node (ref "LED5") (pin "A") (pinfunction "A_A") (pintype "passive"))
      (node (ref "LED6") (pin "A") (pinfunction "A_A") (pintype "passive"))
      (node (ref "LED7") (pin "A") (pinfunction "A_A") (pintype "passive"))
      (node (ref "LED8") (pin "A") (pinfunction "A_A") (pintype "passive"))
      (node (ref "LED9") (pin "A") (pinfunction "A_A") (pintype "passive"))
    )
    (net (code "3") (name "Net-(LED21-C)") (class "Default")
      (node (ref "LED21") (pin "K") (pinfunction "C_K") (pintype "passive"))
      (node (ref "LED22") (pin "K") (pinfunction "C_K") (pintype "passive"))
      (node (ref "LED23") (pin "K") (pinfunction "C_K") (pintype "passive"))
      (node (ref "LED24") (pin "K") (pinfunction "C_K") (pintype "passive"))
      (node (ref "LED25") (pin "K") (pinfunction "C_K") (pintype "passive"))
      (node (ref "LED26") (pin "K") (pinfunction "C_K") (pintype "passive"))
      (node (ref "LED27") (pin "K") (pinfunction "C_K") (pintype "passive"))
      (node (ref "LED28") (pin "K") (pinfunction "C_K") (pintype "passive"))
      (node (ref "LED29") (pin "K") (pinfunction "C_K") (pintype "passive"))
      (node (ref "LED30") (pin "K") (pinfunction "C_K") (pintype "passive"))
      (node (ref "LED31") (pin "K") (pinfunction "C_K") (pintype "passive"))
      (node (ref "LED32") (pin "K") (pinfunction "C_K") (pintype "passive"))
      (node (ref "LED33") (pin "K") (pinfunction "C_K") (pintype "passive"))
      (node (ref "LED34") (pin "K") (pinfunction "C_K") (pintype "passive"))
      (node (ref "LED35") (pin "K") (pinfunction "C_K") (pintype "passive"))
      (node (ref "LED36") (pin "K") (pinfunction "C_K") (pintype "passive"))
      (node (ref "LED37") (pin "K") (pinfunction "C_K") (pintype "passive"))
      (node (ref "LED38") (pin "K") (pinfunction "C_K") (pintype "passive"))
      (node (ref "LED39") (pin "K") (pinfunction "C_K") (pintype "passive"))
      (node (ref "LED40") (pin "K") (pinfunction "C_K") (pintype "passive"))
      (node (ref "R4") (pin "1") (pinfunction "1_1") (pintype "passive"))
    )
    (net (code "4") (name "Net-(LED21-PadA)") (class "Default")
      (node (ref "LED21") (pin "A") (pinfunction "A_A") (pintype "passive"))
      (node (ref "LED22") (pin "A") (pinfunction "A_A") (pintype "passive"))
      (node (ref "LED23") (pin "A") (pinfunction "A_A") (pintype "passive"))
      (node (ref "LED24") (pin "A") (pinfunction "A_A") (pintype "passive"))
      (node (ref "LED25") (pin "A") (pinfunction "A_A") (pintype "passive"))
      (node (ref "LED26") (pin "A") (pinfunction "A_A") (pintype "passive"))
      (node (ref "LED27") (pin "A") (pinfunction "A_A") (pintype "passive"))
      (node (ref "LED28") (pin "A") (pinfunction "A_A") (pintype "passive"))
      (node (ref "LED29") (pin "A") (pinfunction "A_A") (pintype "passive"))
      (node (ref "LED30") (pin "A") (pinfunction "A_A") (pintype "passive"))
      (node (ref "LED31") (pin "A") (pinfunction "A_A") (pintype "passive"))
      (node (ref "LED32") (pin "A") (pinfunction "A_A") (pintype "passive"))
      (node (ref "LED33") (pin "A") (pinfunction "A_A") (pintype "passive"))
      (node (ref "LED34") (pin "A") (pinfunction "A_A") (pintype "passive"))
      (node (ref "LED35") (pin "A") (pinfunction "A_A") (pintype "passive"))
      (node (ref "LED36") (pin "A") (pinfunction "A_A") (pintype "passive"))
      (node (ref "LED37") (pin "A") (pinfunction "A_A") (pintype "passive"))
      (node (ref "LED38") (pin "A") (pinfunction "A_A") (pintype "passive"))
      (node (ref "LED39") (pin "A") (pinfunction "A_A") (pintype "passive"))
      (node (ref "LED40") (pin "A") (pinfunction "A_A") (pintype "passive"))
    )
    (net (code "5") (name "Net-(LED41-C)") (class "Default")
      (node (ref "LED41") (pin "K") (pinfunction "C_K") (pintype "passive"))
      (node (ref "LED42") (pin "K") (pinfunction "C_K") (pintype "passive"))
      (node (ref "LED43") (pin "K") (pinfunction "C_K") (pintype "passive"))
      (node (ref "LED44") (pin "K") (pinfunction "C_K") (pintype "passive"))
      (node (ref "LED45") (pin "K") (pinfunction "C_K") (pintype "passive"))
      (node (ref "LED46") (pin "K") (pinfunction "C_K") (pintype "passive"))
      (node (ref "LED47") (pin "K") (pinfunction "C_K") (pintype "passive"))
      (node (ref "LED48") (pin "K") (pinfunction "C_K") (pintype "passive"))
      (node (ref "LED49") (pin "K") (pinfunction "C_K") (pintype "passive"))
      (node (ref "LED50") (pin "K") (pinfunction "C_K") (pintype "passive"))
      (node (ref "LED51") (pin "K") (pinfunction "C_K") (pintype "passive"))
      (node (ref "LED52") (pin "K") (pinfunction "C_K") (pintype "passive"))
      (node (ref "LED53") (pin "K") (pinfunction "C_K") (pintype "passive"))
      (node (ref "LED54") (pin "K") (pinfunction "C_K") (pintype "passive"))
      (node (ref "LED55") (pin "K") (pinfunction "C_K") (pintype "passive"))
      (node (ref "LED56") (pin "K") (pinfunction "C_K") (pintype "passive"))
      (node (ref "LED57") (pin "K") (pinfunction "C_K") (pintype "passive"))
      (node (ref "LED58") (pin "K") (pinfunction "C_K") (pintype "passive"))
      (node (ref "LED59") (pin "K") (pinfunction "C_K") (pintype "passive"))
      (node (ref "LED60") (pin "K") (pinfunction "C_K") (pintype "passive"))
      (node (ref "R6") (pin "1") (pinfunction "1_1") (pintype "passive"))
    )
    (net (code "6") (name "Net-(LED41-PadA)") (class "Default")
      (node (ref "LED41") (pin "A") (pinfunction "A_A") (pintype "passive"))
      (node (ref "LED42") (pin "A") (pinfunction "A_A") (pintype "passive"))
      (node (ref "LED43") (pin "A") (pinfunction "A_A") (pintype "passive"))
      (node (ref "LED44") (pin "A") (pinfunction "A_A") (pintype "passive"))
      (node (ref "LED45") (pin "A") (pinfunction "A_A") (pintype "passive"))
      (node (ref "LED46") (pin "A") (pinfunction "A_A") (pintype "passive"))
      (node (ref "LED47") (pin "A") (pinfunction "A_A") (pintype "passive"))
      (node (ref "LED48") (pin "A") (pinfunction "A_A") (pintype "passive"))
      (node (ref "LED49") (pin "A") (pinfunction "A_A") (pintype "passive"))
      (node (ref "LED50") (pin "A") (pinfunction "A_A") (pintype "passive"))
      (node (ref "LED51") (pin "A") (pinfunction "A_A") (pintype "passive"))
      (node (ref "LED52") (pin "A") (pinfunction "A_A") (pintype "passive"))
      (node (ref "LED53") (pin "A") (pinfunction "A_A") (pintype "passive"))
      (node (ref "LED54") (pin "A") (pinfunction "A_A") (pintype "passive"))
      (node (ref "LED55") (pin "A") (pinfunction "A_A") (pintype "passive"))
      (node (ref "LED56") (pin "A") (pinfunction "A_A") (pintype "passive"))
      (node (ref "LED57") (pin "A") (pinfunction "A_A") (pintype "passive"))
      (node (ref "LED58") (pin "A") (pinfunction "A_A") (pintype "passive"))
      (node (ref "LED59") (pin "A") (pinfunction "A_A") (pintype "passive"))
      (node (ref "LED60") (pin "A") (pinfunction "A_A") (pintype "passive"))
    )
    (net (code "7") (name "Net-(LED61-C)") (class "Default")
      (node (ref "LED61") (pin "K") (pinfunction "C_K") (pintype "passive"))
      (node (ref "LED62") (pin "K") (pinfunction "C_K") (pintype "passive"))
      (node (ref "LED63") (pin "K") (pinfunction "C_K") (pintype "passive"))
      (node (ref "LED64") (pin "K") (pinfunction "C_K") (pintype "passive"))
      (node (ref "LED65") (pin "K") (pinfunction "C_K") (pintype "passive"))
      (node (ref "LED66") (pin "K") (pinfunction "C_K") (pintype "passive"))
      (node (ref "LED67") (pin "K") (pinfunction "C_K") (pintype "passive"))
      (node (ref "LED68") (pin "K") (pinfunction "C_K") (pintype "passive"))
      (node (ref "LED69") (pin "K") (pinfunction "C_K") (pintype "passive"))
      (node (ref "LED70") (pin "K") (pinfunction "C_K") (pintype "passive"))
      (node (ref "LED71") (pin "K") (pinfunction "C_K") (pintype "passive"))
      (node (ref "LED72") (pin "K") (pinfunction "C_K") (pintype "passive"))
      (node (ref "LED73") (pin "K") (pinfunction "C_K") (pintype "passive"))
      (node (ref "LED74") (pin "K") (pinfunction "C_K") (pintype "passive"))
      (node (ref "LED75") (pin "K") (pinfunction "C_K") (pintype "passive"))
      (node (ref "LED76") (pin "K") (pinfunction "C_K") (pintype "passive"))
      (node (ref "LED77") (pin "K") (pinfunction "C_K") (pintype "passive"))
      (node (ref "LED78") (pin "K") (pinfunction "C_K") (pintype "passive"))
      (node (ref "LED79") (pin "K") (pinfunction "C_K") (pintype "passive"))
      (node (ref "LED80") (pin "K") (pinfunction "C_K") (pintype "passive"))
      (node (ref "R8") (pin "1") (pinfunction "1_1") (pintype "passive"))
    )
    (net (code "8") (name "Net-(LED61-PadA)") (class "Default")
      (node (ref "LED61") (pin "A") (pinfunction "A_A") (pintype "passive"))
      (node (ref "LED62") (pin "A") (pinfunction "A_A") (pintype "passive"))
      (node (ref "LED63") (pin "A") (pinfunction "A_A") (pintype "passive"))
      (node (ref "LED64") (pin "A") (pinfunction "A_A") (pintype "passive"))
      (node (ref "LED65") (pin "A") (pinfunction "A_A") (pintype "passive"))
      (node (ref "LED66") (pin "A") (pinfunction "A_A") (pintype "passive"))
      (node (ref "LED67") (pin "A") (pinfunction "A_A") (pintype "passive"))
      (node (ref "LED68") (pin "A") (pinfunction "A_A") (pintype "passive"))
      (node (ref "LED69") (pin "A") (pinfunction "A_A") (pintype "passive"))
      (node (ref "LED70") (pin "A") (pinfunction "A_A") (pintype "passive"))
      (node (ref "LED71") (pin "A") (pinfunction "A_A") (pintype "passive"))
      (node (ref "LED72") (pin "A") (pinfunction "A_A") (pintype "passive"))
      (node (ref "LED73") (pin "A") (pinfunction "A_A") (pintype "passive"))
      (node (ref "LED74") (pin "A") (pinfunction "A_A") (pintype "passive"))
      (node (ref "LED75") (pin "A") (pinfunction "A_A") (pintype "passive"))
      (node (ref "LED76") (pin "A") (pinfunction "A_A") (pintype "passive"))
      (node (ref "LED77") (pin "A") (pinfunction "A_A") (pintype "passive"))
      (node (ref "LED78") (pin "A") (pinfunction "A_A") (pintype "passive"))
      (node (ref "LED79") (pin "A") (pinfunction "A_A") (pintype "passive"))
      (node (ref "LED80") (pin "A") (pinfunction "A_A") (pintype "passive"))
    )
    (net (code "9") (name "Net-(LED100-C)") (class "Default")
      (node (ref "LED100") (pin "K") (pinfunction "C_K") (pintype "passive"))
      (node (ref "LED81") (pin "K") (pinfunction "C_K") (pintype "passive"))
      (node (ref "LED82") (pin "K") (pinfunction "C_K") (pintype "passive"))
      (node (ref "LED83") (pin "K") (pinfunction "C_K") (pintype "passive"))
      (node (ref "LED84") (pin "K") (pinfunction "C_K") (pintype "passive"))
      (node (ref "LED85") (pin "K") (pinfunction "C_K") (pintype "passive"))
      (node (ref "LED86") (pin "K") (pinfunction "C_K") (pintype "passive"))
      (node (ref "LED87") (pin "K") (pinfunction "C_K") (pintype "passive"))
      (node (ref "LED88") (pin "K") (pinfunction "C_K") (pintype "passive"))
      (node (ref "LED89") (pin "K") (pinfunction "C_K") (pintype "passive"))
      (node (ref "LED90") (pin "K") (pinfunction "C_K") (pintype "passive"))
      (node (ref "LED91") (pin "K") (pinfunction "C_K") (pintype "passive"))
      (node (ref "LED92") (pin "K") (pinfunction "C_K") (pintype "passive"))
      (node (ref "LED93") (pin "K") (pinfunction "C_K") (pintype "passive"))
      (node (ref "LED94") (pin "K") (pinfunction "C_K") (pintype "passive"))
      (node (ref "LED95") (pin "K") (pinfunction "C_K") (pintype "passive"))
      (node (ref "LED96") (pin "K") (pinfunction "C_K") (pintype "passive"))
      (node (ref "LED97") (pin "K") (pinfunction "C_K") (pintype "passive"))
      (node (ref "LED98") (pin "K") (pinfunction "C_K") (pintype "passive"))
      (node (ref "LED99") (pin "K") (pinfunction "C_K") (pintype "passive"))
      (node (ref "R10") (pin "1") (pinfunction "1_1") (pintype "passive"))
    )
    (net (code "10") (name "Net-(LED100-PadA)") (class "Default")
      (node (ref "LED100") (pin "A") (pinfunction "A_A") (pintype "passive"))
      (node (ref "LED81") (pin "A") (pinfunction "A_A") (pintype "passive"))
      (node (ref "LED82") (pin "A") (pinfunction "A_A") (pintype "passive"))
      (node (ref "LED83") (pin "A") (pinfunction "A_A") (pintype "passive"))
      (node (ref "LED84") (pin "A") (pinfunction "A_A") (pintype "passive"))
      (node (ref "LED85") (pin "A") (pinfunction "A_A") (pintype "passive"))
      (node (ref "LED86") (pin "A") (pinfunction "A_A") (pintype "passive"))
      (node (ref "LED87") (pin "A") (pinfunction "A_A") (pintype "passive"))
      (node (ref "LED88") (pin "A") (pinfunction "A_A") (pintype "passive"))
      (node (ref "LED89") (pin "A") (pinfunction "A_A") (pintype "passive"))
      (node (ref "LED90") (pin "A") (pinfunction "A_A") (pintype "passive"))
      (node (ref "LED91") (pin "A") (pinfunction "A_A") (pintype "passive"))
      (node (ref "LED92") (pin "A") (pinfunction "A_A") (pintype "passive"))
      (node (ref "LED93") (pin "A") (pinfunction "A_A") (pintype "passive"))
      (node (ref "LED94") (pin "A") (pinfunction "A_A") (pintype "passive"))
      (node (ref "LED95") (pin "A") (pinfunction "A_A") (pintype "passive"))
      (node (ref "LED96") (pin "A") (pinfunction "A_A") (pintype "passive"))
      (node (ref "LED97") (pin "A") (pinfunction "A_A") (pintype "passive"))
      (node (ref "LED98") (pin "A") (pinfunction "A_A") (pintype "passive"))
      (node (ref "LED99") (pin "A") (pinfunction "A_A") (pintype "passive"))
    )
    (net (code "11") (name "Net-(LED101-C)") (class "Default")
      (node (ref "LED101") (pin "K") (pinfunction "C_K") (pintype "passive"))
      (node (ref "LED102") (pin "K") (pinfunction "C_K") (pintype "passive"))
      (node (ref "LED103") (pin "K") (pinfunction "C_K") (pintype "passive"))
      (node (ref "LED104") (pin "K") (pinfunction "C_K") (pintype "passive"))
      (node (ref "LED105") (pin "K") (pinfunction "C_K") (pintype "passive"))
      (node (ref "LED106") (pin "K") (pinfunction "C_K") (pintype "passive"))
      (node (ref "LED107") (pin "K") (pinfunction "C_K") (pintype "passive"))
      (node (ref "LED108") (pin "K") (pinfunction "C_K") (pintype "passive"))
      (node (ref "LED109") (pin "K") (pinfunction "C_K") (pintype "passive"))
      (node (ref "LED110") (pin "K") (pinfunction "C_K") (pintype "passive"))
      (node (ref "LED111") (pin "K") (pinfunction "C_K") (pintype "passive"))
      (node (ref "LED112") (pin "K") (pinfunction "C_K") (pintype "passive"))
      (node (ref "LED113") (pin "K") (pinfunction "C_K") (pintype "passive"))
      (node (ref "LED114") (pin "K") (pinfunction "C_K") (pintype "passive"))
      (node (ref "LED115") (pin "K") (pinfunction "C_K") (pintype "passive"))
      (node (ref "LED116") (pin "K") (pinfunction "C_K") (pintype "passive"))
      (node (ref "LED117") (pin "K") (pinfunction "C_K") (pintype "passive"))
      (node (ref "LED118") (pin "K") (pinfunction "C_K") (pintype "passive"))
      (node (ref "LED119") (pin "K") (pinfunction "C_K") (pintype "passive"))
      (node (ref "LED120") (pin "K") (pinfunction "C_K") (pintype "passive"))
      (node (ref "R12") (pin "1") (pinfunction "1_1") (pintype "passive"))
    )
    (net (code "12") (name "Net-(LED101-PadA)") (class "Default")
      (node (ref "LED101") (pin "A") (pinfunction "A_A") (pintype "passive"))
      (node (ref "LED102") (pin "A") (pinfunction "A_A") (pintype "passive"))
      (node (ref "LED103") (pin "A") (pinfunction "A_A") (pintype "passive"))
      (node (ref "LED104") (pin "A") (pinfunction "A_A") (pintype "passive"))
      (node (ref "LED105") (pin "A") (pinfunction "A_A") (pintype "passive"))
      (node (ref "LED106") (pin "A") (pinfunction "A_A") (pintype "passive"))
      (node (ref "LED107") (pin "A") (pinfunction "A_A") (pintype "passive"))
      (node (ref "LED108") (pin "A") (pinfunction "A_A") (pintype "passive"))
      (node (ref "LED109") (pin "A") (pinfunction "A_A") (pintype "passive"))
      (node (ref "LED110") (pin "A") (pinfunction "A_A") (pintype "passive"))
      (node (ref "LED111") (pin "A") (pinfunction "A_A") (pintype "passive"))
      (node (ref "LED112") (pin "A") (pinfunction "A_A") (pintype "passive"))
      (node (ref "LED113") (pin "A") (pinfunction "A_A") (pintype "passive"))
      (node (ref "LED114") (pin "A") (pinfunction "A_A") (pintype "passive"))
      (node (ref "LED115") (pin "A") (pinfunction "A_A") (pintype "passive"))
      (node (ref "LED116") (pin "A") (pinfunction "A_A") (pintype "passive"))
      (node (ref "LED117") (pin "A") (pinfunction "A_A") (pintype "passive"))
      (node (ref "LED118") (pin "A") (pinfunction "A_A") (pintype "passive"))
      (node (ref "LED119") (pin "A") (pinfunction "A_A") (pintype "passive"))
      (node (ref "LED120") (pin "A") (pinfunction "A_A") (pintype "passive"))
    )
    (net (code "13") (name "Net-(LED121-C)") (class "Default")
      (node (ref "LED121") (pin "K") (pinfunction "C_K") (pintype "passive"))
      (node (ref "LED122") (pin "K") (pinfunction "C_K") (pintype "passive"))
      (node (ref "LED123") (pin "K") (pinfunction "C_K") (pintype "passive"))
      (node (ref "LED124") (pin "K") (pinfunction "C_K") (pintype "passive"))
      (node (ref "LED125") (pin "K") (pinfunction "C_K") (pintype "passive"))
      (node (ref "LED126") (pin "K") (pinfunction "C_K") (pintype "passive"))
      (node (ref "LED127") (pin "K") (pinfunction "C_K") (pintype "passive"))
      (node (ref "LED128") (pin "K") (pinfunction "C_K") (pintype "passive"))
      (node (ref "LED129") (pin "K") (pinfunction "C_K") (pintype "passive"))
      (node (ref "LED130") (pin "K") (pinfunction "C_K") (pintype "passive"))
      (node (ref "LED131") (pin "K") (pinfunction "C_K") (pintype "passive"))
      (node (ref "LED132") (pin "K") (pinfunction "C_K") (pintype "passive"))
      (node (ref "LED133") (pin "K") (pinfunction "C_K") (pintype "passive"))
      (node (ref "LED134") (pin "K") (pinfunction "C_K") (pintype "passive"))
      (node (ref "LED135") (pin "K") (pinfunction "C_K") (pintype "passive"))
      (node (ref "LED136") (pin "K") (pinfunction "C_K") (pintype "passive"))
      (node (ref "LED137") (pin "K") (pinfunction "C_K") (pintype "passive"))
      (node (ref "LED138") (pin "K") (pinfunction "C_K") (pintype "passive"))
      (node (ref "LED139") (pin "K") (pinfunction "C_K") (pintype "passive"))
      (node (ref "LED140") (pin "K") (pinfunction "C_K") (pintype "passive"))
      (node (ref "R14") (pin "1") (pinfunction "1_1") (pintype "passive"))
    )
    (net (code "14") (name "Net-(LED121-PadA)") (class "Default")
      (node (ref "LED121") (pin "A") (pinfunction "A_A") (pintype "passive"))
      (node (ref "LED122") (pin "A") (pinfunction "A_A") (pintype "passive"))
      (node (ref "LED123") (pin "A") (pinfunction "A_A") (pintype "passive"))
      (node (ref "LED124") (pin "A") (pinfunction "A_A") (pintype "passive"))
      (node (ref "LED125") (pin "A") (pinfunction "A_A") (pintype "passive"))
      (node (ref "LED126") (pin "A") (pinfunction "A_A") (pintype "passive"))
      (node (ref "LED127") (pin "A") (pinfunction "A_A") (pintype "passive"))
      (node (ref "LED128") (pin "A") (pinfunction "A_A") (pintype "passive"))
      (node (ref "LED129") (pin "A") (pinfunction "A_A") (pintype "passive"))
      (node (ref "LED130") (pin "A") (pinfunction "A_A") (pintype "passive"))
      (node (ref "LED131") (pin "A") (pinfunction "A_A") (pintype "passive"))
      (node (ref "LED132") (pin "A") (pinfunction "A_A") (pintype "passive"))
      (node (ref "LED133") (pin "A") (pinfunction "A_A") (pintype "passive"))
      (node (ref "LED134") (pin "A") (pinfunction "A_A") (pintype "passive"))
      (node (ref "LED135") (pin "A") (pinfunction "A_A") (pintype "passive"))
      (node (ref "LED136") (pin "A") (pinfunction "A_A") (pintype "passive"))
      (node (ref "LED137") (pin "A") (pinfunction "A_A") (pintype "passive"))
      (node (ref "LED138") (pin "A") (pinfunction "A_A") (pintype "passive"))
      (node (ref "LED139") (pin "A") (pinfunction "A_A") (pintype "passive"))
      (node (ref "LED140") (pin "A") (pinfunction "A_A") (pintype "passive"))
    )
    (net (code "15") (name "Net-(R1-Pad2)") (class "Default")
      (node (ref "R1") (pin "2") (pinfunction "2_2") (pintype "passive"))
      (node (ref "T1") (pin "C") (pinfunction "C_C") (pintype "passive"))
    )
    (net (code "16") (name "Net-(R2-Pad1)") (class "Default")
      (node (ref "R2") (pin "1") (pinfunction "1_1") (pintype "passive"))
      (node (ref "T1") (pin "B") (pinfunction "B_B") (pintype "passive"))
    )
    (net (code "17") (name "Net-(R3-Pad1)") (class "Default")
      (node (ref "R3") (pin "1") (pinfunction "1_1") (pintype "passive"))
      (node (ref "T2") (pin "B") (pinfunction "B_B") (pintype "passive"))
    )
    (net (code "18") (name "Net-(R4-Pad2)") (class "Default")
      (node (ref "R4") (pin "2") (pinfunction "2_2") (pintype "passive"))
      (node (ref "T2") (pin "C") (pinfunction "C_C") (pintype "passive"))
    )
    (net (code "19") (name "Net-(R5-Pad1)") (class "Default")
      (node (ref "R5") (pin "1") (pinfunction "1_1") (pintype "passive"))
      (node (ref "T3") (pin "B") (pinfunction "B_B") (pintype "passive"))
    )
    (net (code "20") (name "Net-(R6-Pad2)") (class "Default")
      (node (ref "R6") (pin "2") (pinfunction "2_2") (pintype "passive"))
      (node (ref "T3") (pin "C") (pinfunction "C_C") (pintype "passive"))
    )
    (net (code "21") (name "Net-(R7-Pad1)") (class "Default")
      (node (ref "R7") (pin "1") (pinfunction "1_1") (pintype "passive"))
      (node (ref "T4") (pin "B") (pinfunction "B_B") (pintype "passive"))
    )
    (net (code "22") (name "Net-(R8-Pad2)") (class "Default")
      (node (ref "R8") (pin "2") (pinfunction "2_2") (pintype "passive"))
      (node (ref "T4") (pin "C") (pinfunction "C_C") (pintype "passive"))
    )
    (net (code "23") (name "Net-(R9-Pad1)") (class "Default")
      (node (ref "R9") (pin "1") (pinfunction "1_1") (pintype "passive"))
      (node (ref "T5") (pin "B") (pinfunction "B_B") (pintype "passive"))
    )
    (net (code "24") (name "Net-(R10-Pad2)") (class "Default")
      (node (ref "R10") (pin "2") (pinfunction "2_2") (pintype "passive"))
      (node (ref "T5") (pin "C") (pinfunction "C_C") (pintype "passive"))
    )
    (net (code "25") (name "Net-(R11-Pad1)") (class "Default")
      (node (ref "R11") (pin "1") (pinfunction "1_1") (pintype "passive"))
      (node (ref "T6") (pin "B") (pinfunction "B_B") (pintype "passive"))
    )
    (net (code "26") (name "Net-(R12-Pad2)") (class "Default")
      (node (ref "R12") (pin "2") (pinfunction "2_2") (pintype "passive"))
      (node (ref "T6") (pin "C") (pinfunction "C_C") (pintype "passive"))
    )
    (net (code "27") (name "Net-(R13-Pad1)") (class "Default")
      (node (ref "R13") (pin "1") (pinfunction "1_1") (pintype "passive"))
      (node (ref "T7") (pin "B") (pinfunction "B_B") (pintype "passive"))
    )
    (net (code "28") (name "Net-(R14-Pad2)") (class "Default")
      (node (ref "R14") (pin "2") (pinfunction "2_2") (pintype "passive"))
      (node (ref "T7") (pin "C") (pinfunction "C_C") (pintype "passive"))
    )
    (net (code "30") (name "unconnected-(MGT2-PadP$1)") (class "Default")
      (node (ref "MGT2") (pin "P$1") (pinfunction "P$1_P$1") (pintype "bidirectional"))
    )
    (net (code "31") (name "unconnected-(MGT3-PadP$1)") (class "Default")
      (node (ref "MGT3") (pin "P$1") (pinfunction "P$1_P$1") (pintype "bidirectional"))
    )
    (net (code "32") (name "unconnected-(MGT4-PadP$1)") (class "Default")
      (node (ref "MGT4") (pin "P$1") (pinfunction "P$1_P$1") (pintype "bidirectional"))
    )
    (net (code "33") (name "unconnected-(MGT6-PadP$1)") (class "Default")
      (node (ref "MGT6") (pin "P$1") (pinfunction "P$1_P$1") (pintype "bidirectional"))
    )
    (net (code "34") (name "unconnected-(MGT8-PadP$1)") (class "Default")
      (node (ref "MGT8") (pin "P$1") (pinfunction "P$1_P$1") (pintype "bidirectional"))
    )
    (net (code "35") (name "unconnected-(MGT9-PadP$1)") (class "Default")
      (node (ref "MGT9") (pin "P$1") (pinfunction "P$1_P$1") (pintype "bidirectional"))
    )
    (net (code "36") (name "unconnected-(R2-Pad2)") (class "Default")
      (node (ref "R2") (pin "2") (pinfunction "2_2") (pintype "passive"))
    )
    (net (code "37") (name "unconnected-(R3-Pad2)") (class "Default")
      (node (ref "R3") (pin "2") (pinfunction "2_2") (pintype "passive"))
    )
    (net (code "38") (name "unconnected-(R5-Pad2)") (class "Default")
      (node (ref "R5") (pin "2") (pinfunction "2_2") (pintype "passive"))
    )
    (net (code "39") (name "unconnected-(R7-Pad2)") (class "Default")
      (node (ref "R7") (pin "2") (pinfunction "2_2") (pintype "passive"))
    )
    (net (code "40") (name "unconnected-(R9-Pad2)") (class "Default")
      (node (ref "R9") (pin "2") (pinfunction "2_2") (pintype "passive"))
    )
    (net (code "41") (name "unconnected-(R11-Pad2)") (class "Default")
      (node (ref "R11") (pin "2") (pinfunction "2_2") (pintype "passive"))
    )
    (net (code "42") (name "unconnected-(R13-Pad2)") (class "Default")
      (node (ref "R13") (pin "2") (pinfunction "2_2") (pintype "passive"))
    )
    (net (code "43") (name "unconnected-(T1-PadE)") (class "Default")
      (node (ref "T1") (pin "E") (pinfunction "E_E") (pintype "passive"))
    )
    (net (code "44") (name "unconnected-(T2-PadE)") (class "Default")
      (node (ref "T2") (pin "E") (pinfunction "E_E") (pintype "passive"))
    )
    (net (code "45") (name "unconnected-(T3-PadE)") (class "Default")
      (node (ref "T3") (pin "E") (pinfunction "E_E") (pintype "passive"))
    )
    (net (code "46") (name "unconnected-(T4-PadE)") (class "Default")
      (node (ref "T4") (pin "E") (pinfunction "E_E") (pintype "passive"))
    )
    (net (code "47") (name "unconnected-(T5-PadE)") (class "Default")
      (node (ref "T5") (pin "E") (pinfunction "E_E") (pintype "passive"))
    )
    (net (code "48") (name "unconnected-(T6-PadE)") (class "Default")
      (node (ref "T6") (pin "E") (pinfunction "E_E") (pintype "passive"))
    )
    (net (code "49") (name "unconnected-(T7-PadE)") (class "Default")
      (node (ref "T7") (pin "E") (pinfunction "E_E") (pintype "passive"))
    )
    (net (code "50") (name "unconnected-(X1-P1-PadL1)") (class "Default")
      (node (ref "X1") (pin "L1") (pinfunction "P1_L1") (pintype "bidirectional"))
    )
    (net (code "51") (name "unconnected-(X1-P2-PadL2)") (class "Default")
      (node (ref "X1") (pin "L2") (pinfunction "P2_L2") (pintype "bidirectional"))
    )
  )
)
